# easyeda_hackercard.net
KiCad netlist of a schematic drawn in EasyEDA
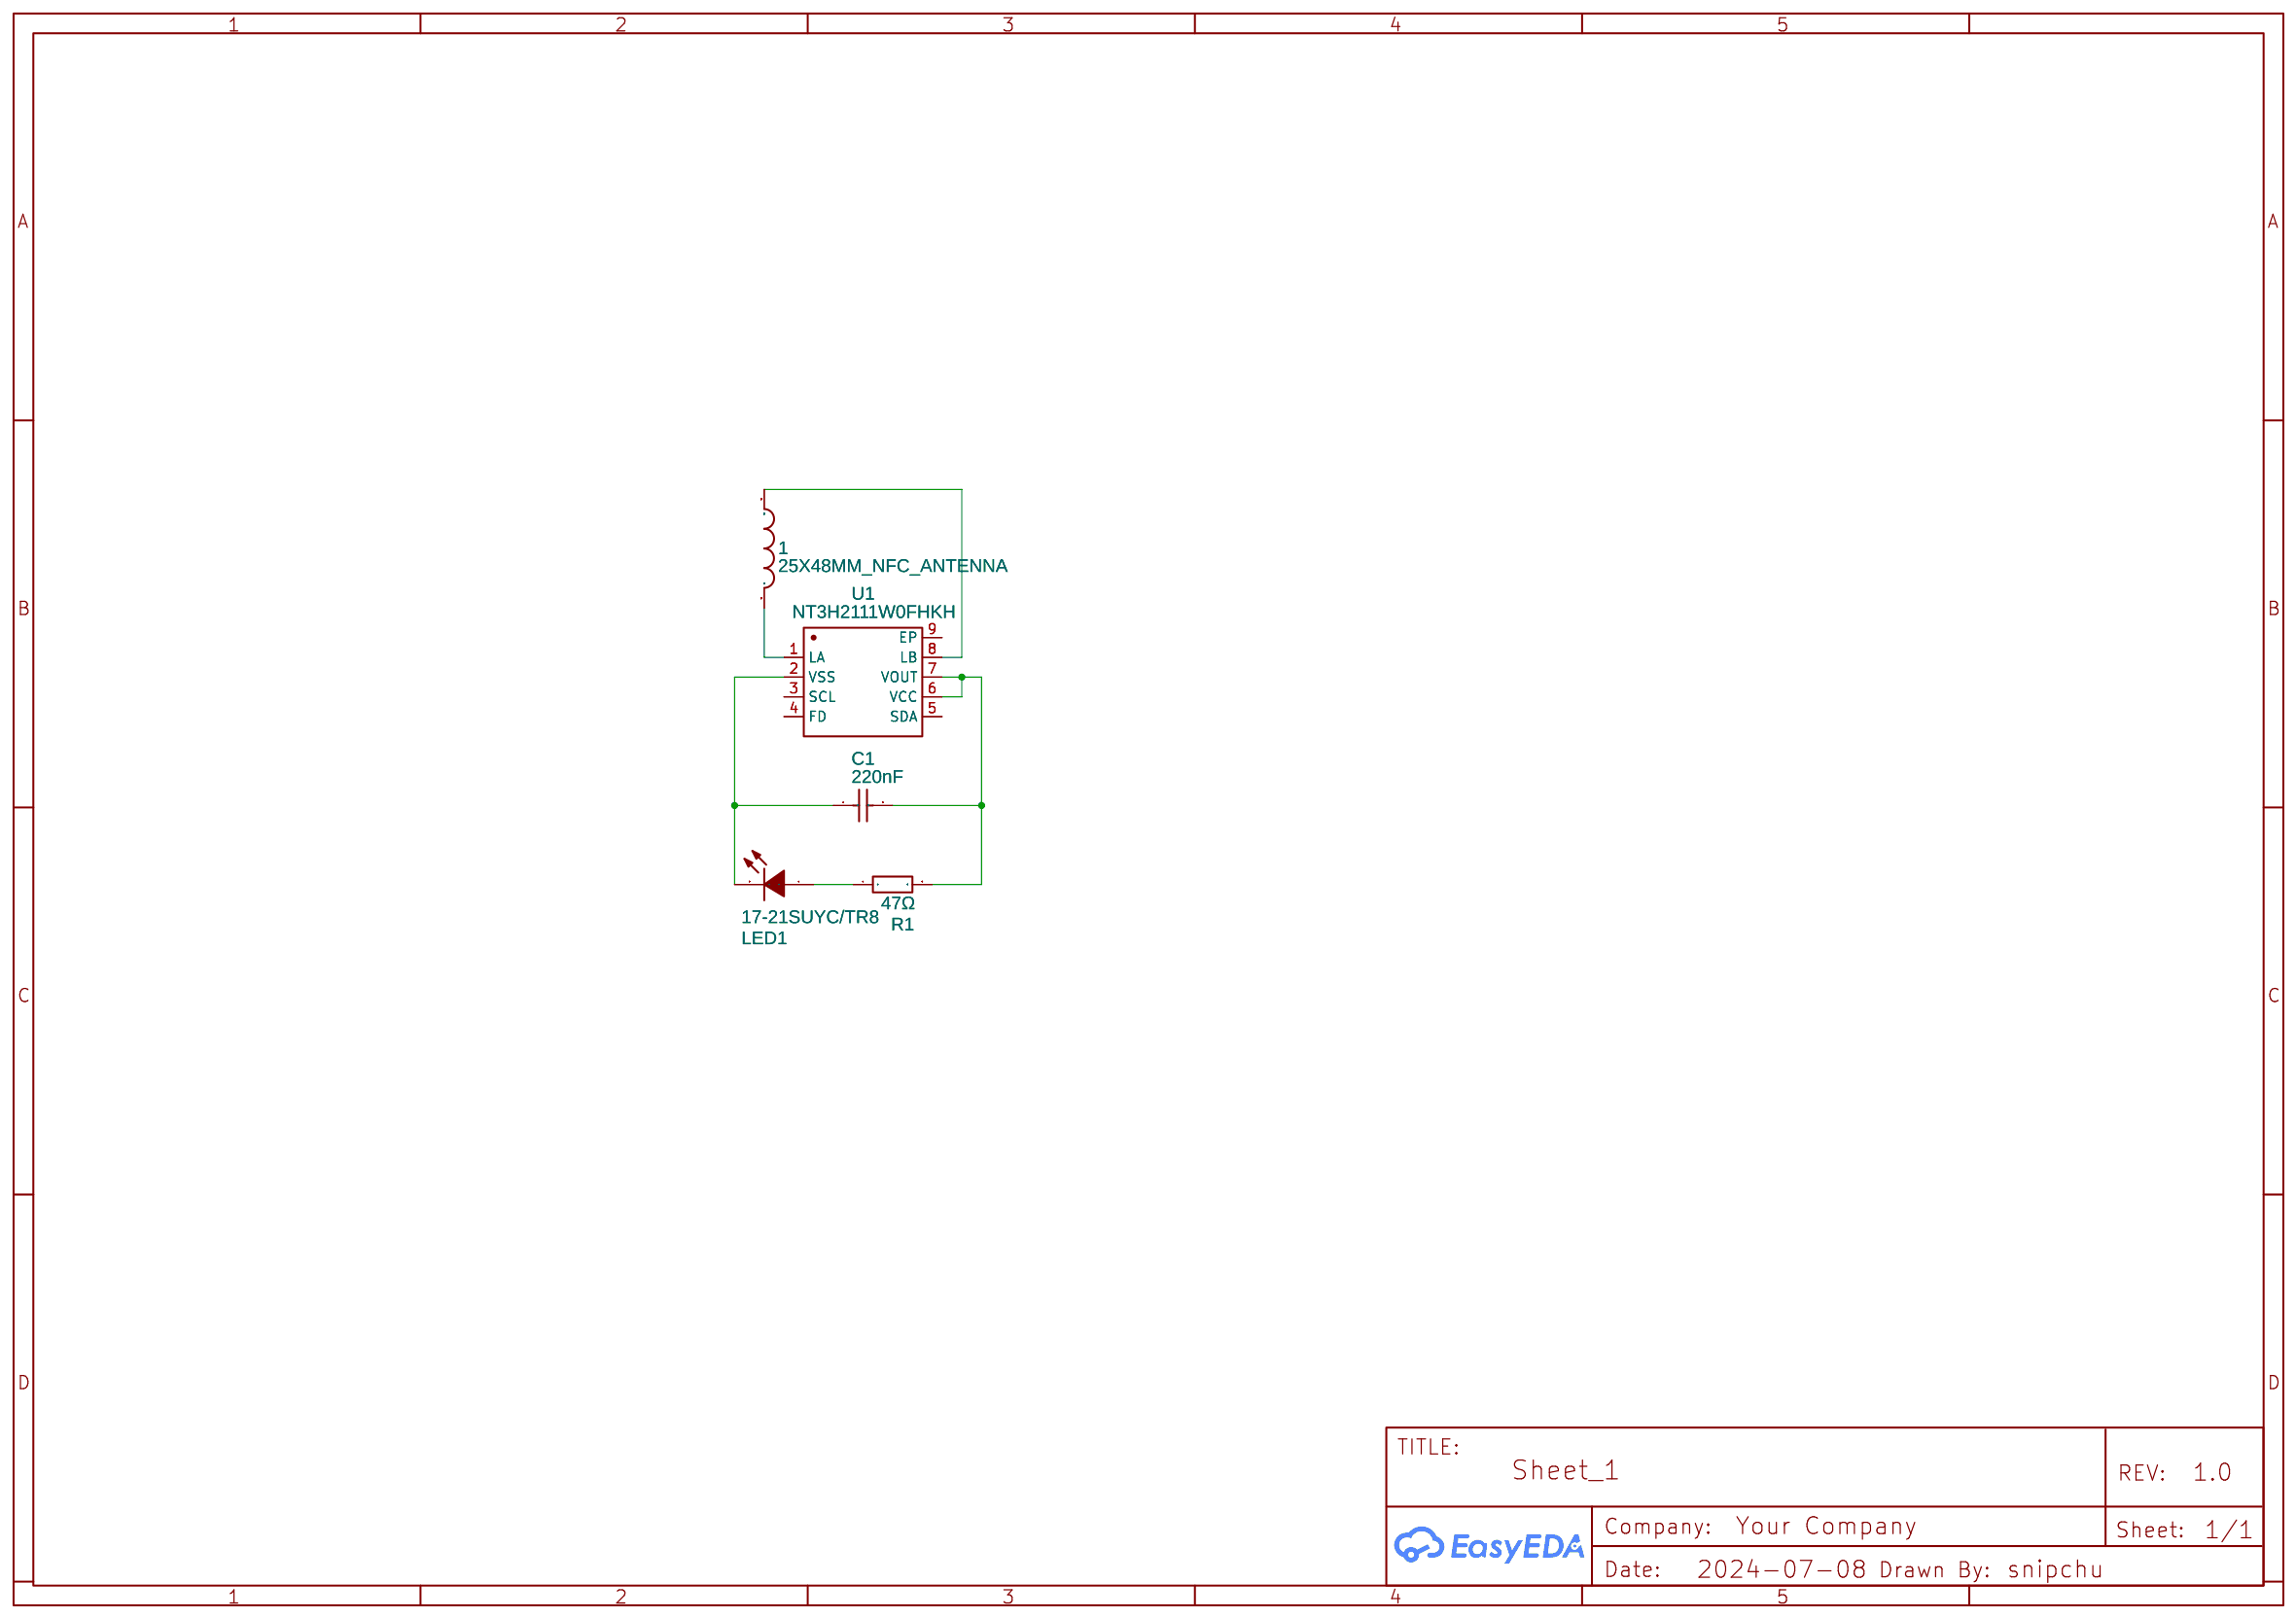
[diagram p0: schematic sheet]

(export (version "E")
  (design (tool "Eeschema 10.0.6"))
  (components
    (comp (ref "1") (value "25X48MM_NFC_ANTENNA") (libsource (lib "") (part "25X48MM_NFC_ANTENNA")))
    (comp (ref "C1")
      (value "220nF")
      (fields
        (field (name "Manufacturer Part") "CL10B224KA8NNNC")
        (field (name "Manufacturer") "SAMSUNG(三星)")
      )
      (libsource (lib "") (part "CL10B224KA8NNNC"))
    )
    (comp (ref "LED1")
      (value "17-21SUYC/TR8")
      (fields (field (name "Manufacturer Part") "KT-0805黄灯") (field (name "Manufacturer") "KENTO"))
      (libsource (lib "") (part "17-21SUYC/TR8"))
    )
    (comp (ref "R1")
      (value "47Ω")
      (fields
        (field (name "Manufacturer Part") "0603WAF470JT5E")
        (field (name "Manufacturer") "UNI-ROYAL(厚声)")
      )
      (libsource (lib "") (part "0603WAF470JT5E"))
    )
    (comp (ref "U1")
      (value "NT3H2111W0FHKH")
      (fields (field (name "Manufacturer") "NXP(恩智浦)"))
      (libsource (lib "") (part "NT3H2111W0FHKH"))
    )
  )
  (nets
    (net (code "1") (name "Net-(LED1-+)") (class "Default")
      (node (ref "LED1") (pin "1") (pinfunction "+_1") (pintype "unspecified"))
      (node (ref "R1") (pin "1") (pinfunction "1_1") (pintype "input"))
    )
    (net (code "2") (name "Net-(LED1--)") (class "Default")
      (node (ref "C1") (pin "1") (pinfunction "1_1") (pintype "input"))
      (node (ref "LED1") (pin "2") (pinfunction "-_2") (pintype "unspecified"))
      (node (ref "U1") (pin "2") (pinfunction "VSS_2") (pintype "unspecified"))
    )
    (net (code "3") (name "Net-(U1-LA)") (class "Default")
      (node (ref "1") (pin "P$2") (pinfunction "P$2_P$2") (pintype "bidirectional"))
      (node (ref "U1") (pin "1") (pinfunction "LA_1") (pintype "unspecified"))
    )
    (net (code "4") (name "Net-(U1-LB)") (class "Default")
      (node (ref "1") (pin "P$1") (pinfunction "P$1_P$1") (pintype "bidirectional"))
      (node (ref "U1") (pin "8") (pinfunction "LB_8") (pintype "unspecified"))
    )
    (net (code "5") (name "Net-(U1-VCC)") (class "Default")
      (node (ref "C1") (pin "2") (pinfunction "2_2") (pintype "input"))
      (node (ref "R1") (pin "2") (pinfunction "2_2") (pintype "input"))
      (node (ref "U1") (pin "6") (pinfunction "VCC_6") (pintype "unspecified"))
      (node (ref "U1") (pin "7") (pinfunction "VOUT_7") (pintype "unspecified"))
    )
    (net (code "6") (name "unconnected-(U1-EP-Pad9)") (class "Default")
      (node (ref "U1") (pin "9") (pinfunction "EP_9") (pintype "unspecified"))
    )
    (net (code "7") (name "unconnected-(U1-FD-Pad4)") (class "Default")
      (node (ref "U1") (pin "4") (pinfunction "FD_4") (pintype "unspecified"))
    )
    (net (code "8") (name "unconnected-(U1-SCL-Pad3)") (class "Default")
      (node (ref "U1") (pin "3") (pinfunction "SCL_3") (pintype "unspecified"))
    )
    (net (code "9") (name "unconnected-(U1-SDA-Pad5)") (class "Default")
      (node (ref "U1") (pin "5") (pinfunction "SDA_5") (pintype "unspecified"))
    )
  )
)
